# v11.net
KiCad netlist of a schematic drawn in EAGLE
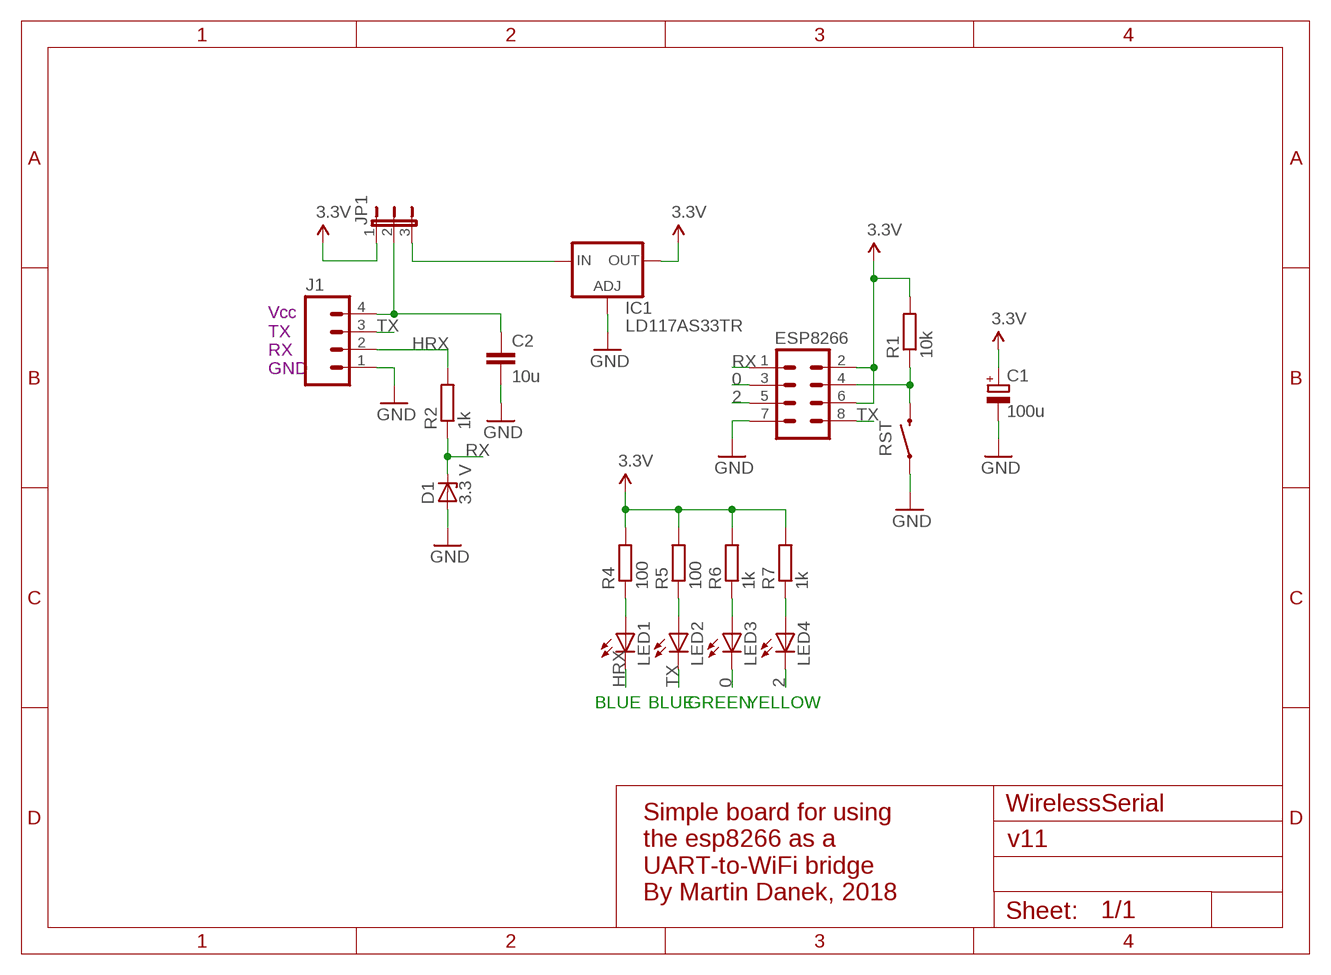
[diagram p0: schematic, sheet 1]

(export (version "E")
  (design (tool "Eeschema 10.0.6"))
  (components
    (comp (ref "C1")
      (value "100u")
      (footprint "eagle-import:E2,5-6E")
      (libsource (lib "eagle-import") (part "CPOL-EUE2,5-6E"))
    )
    (comp (ref "C2")
      (value "10u")
      (footprint "eagle-import:C1206")
      (libsource (lib "eagle-import") (part "C-EUC1206"))
    )
    (comp (ref "D1")
      (value "3.3 V")
      (footprint "eagle-import:DO35Z10")
      (libsource (lib "eagle-import") (part "ZENER-DIODEDO35Z10"))
    )
    (comp (ref "ESP8266")
      (value "M04X2")
      (footprint "eagle-import:2X4")
      (libsource (lib "eagle-import") (part "M04X2"))
    )
    (comp (ref "IC1")
      (value "LD117AS33TR")
      (footprint "eagle-import:SOT223")
      (libsource (lib "eagle-import") (part "LD117A?S33TR"))
    )
    (comp (ref "J1")
      (value "M04LONGPADS")
      (footprint "eagle-import:1X04_LONGPADS")
      (libsource (lib "eagle-import") (part "M04LONGPADS"))
    )
    (comp (ref "JP1")
      (value "JP2E")
      (footprint "eagle-import:JP2")
      (libsource (lib "eagle-import") (part "JP2E"))
    )
    (comp (ref "LED1")
      (value "LEDSML1206")
      (footprint "eagle-import:SML1206")
      (libsource (lib "eagle-import") (part "LEDSML1206"))
    )
    (comp (ref "LED2")
      (value "LEDSML1206")
      (footprint "eagle-import:SML1206")
      (libsource (lib "eagle-import") (part "LEDSML1206"))
    )
    (comp (ref "LED3")
      (value "LEDSML1206")
      (footprint "eagle-import:SML1206")
      (libsource (lib "eagle-import") (part "LEDSML1206"))
    )
    (comp (ref "LED4")
      (value "LEDSML1206")
      (footprint "eagle-import:SML1206")
      (libsource (lib "eagle-import") (part "LEDSML1206"))
    )
    (comp (ref "R1")
      (value "10k")
      (footprint "eagle-import:R1206")
      (libsource (lib "eagle-import") (part "R-EU_R1206"))
    )
    (comp (ref "R2")
      (value "1k")
      (footprint "eagle-import:R1206")
      (libsource (lib "eagle-import") (part "R-EU_R1206"))
    )
    (comp (ref "R4")
      (value "100")
      (footprint "eagle-import:R1206")
      (libsource (lib "eagle-import") (part "R-EU_R1206"))
    )
    (comp (ref "R5")
      (value "100")
      (footprint "eagle-import:R1206")
      (libsource (lib "eagle-import") (part "R-EU_R1206"))
    )
    (comp (ref "R6")
      (value "1k")
      (footprint "eagle-import:R1206")
      (libsource (lib "eagle-import") (part "R-EU_R1206"))
    )
    (comp (ref "R7")
      (value "1k")
      (footprint "eagle-import:R1206")
      (libsource (lib "eagle-import") (part "R-EU_R1206"))
    )
    (comp (ref "RST")
      (value "SWITCH-MOMENTARY-2PTH")
      (footprint "eagle-import:TACTILE-PTH")
      (libsource (lib "eagle-import") (part "SWITCH-MOMENTARY-2PTH"))
    )
  )
  (nets
    (net (code "1") (name "/0") (class "Default")
      (node (ref "ESP8266") (pin "3") (pinfunction "3_3") (pintype "passive"))
      (node (ref "LED3") (pin "C") (pinfunction "C_C") (pintype "passive"))
    )
    (net (code "2") (name "/2") (class "Default")
      (node (ref "ESP8266") (pin "5") (pinfunction "5_5") (pintype "passive"))
      (node (ref "LED4") (pin "C") (pinfunction "C_C") (pintype "passive"))
    )
    (net (code "3") (name "/HRX") (class "Default")
      (node (ref "J1") (pin "2") (pinfunction "2_2") (pintype "passive"))
      (node (ref "LED1") (pin "C") (pinfunction "C_C") (pintype "passive"))
      (node (ref "R2") (pin "2") (pinfunction "2_2") (pintype "passive"))
    )
    (net (code "4") (name "/RX") (class "Default")
      (node (ref "D1") (pin "C") (pinfunction "C_C") (pintype "passive"))
      (node (ref "ESP8266") (pin "1") (pinfunction "1_1") (pintype "passive"))
      (node (ref "R2") (pin "1") (pinfunction "1_1") (pintype "passive"))
    )
    (net (code "5") (name "/TX") (class "Default")
      (node (ref "ESP8266") (pin "8") (pinfunction "8_8") (pintype "passive"))
      (node (ref "J1") (pin "3") (pinfunction "3_3") (pintype "passive"))
      (node (ref "LED2") (pin "C") (pinfunction "C_C") (pintype "passive"))
    )
    (net (code "6") (name "3.3V") (class "Default")
      (node (ref "C1") (pin "+") (pinfunction "+_+") (pintype "passive"))
      (node (ref "ESP8266") (pin "2") (pinfunction "2_2") (pintype "passive"))
      (node (ref "ESP8266") (pin "6") (pinfunction "6_6") (pintype "passive"))
      (node (ref "IC1") (pin "4") (pinfunction "OUT_4") (pintype "passive"))
      (node (ref "JP1") (pin "1") (pinfunction "1_1") (pintype "passive"))
      (node (ref "R1") (pin "2") (pinfunction "2_2") (pintype "passive"))
      (node (ref "R4") (pin "2") (pinfunction "2_2") (pintype "passive"))
      (node (ref "R5") (pin "2") (pinfunction "2_2") (pintype "passive"))
      (node (ref "R6") (pin "2") (pinfunction "2_2") (pintype "passive"))
      (node (ref "R7") (pin "2") (pinfunction "2_2") (pintype "passive"))
    )
    (net (code "7") (name "GND") (class "Default")
      (node (ref "C1") (pin "-") (pinfunction "-_-") (pintype "passive"))
      (node (ref "C2") (pin "2") (pinfunction "2_2") (pintype "passive"))
      (node (ref "D1") (pin "A") (pinfunction "A_A") (pintype "passive"))
      (node (ref "ESP8266") (pin "7") (pinfunction "7_7") (pintype "passive"))
      (node (ref "IC1") (pin "1") (pinfunction "ADJ_1") (pintype "input"))
      (node (ref "J1") (pin "1") (pinfunction "1_1") (pintype "passive"))
      (node (ref "RST") (pin "1") (pinfunction "1_1") (pintype "passive"))
    )
    (net (code "8") (name "Net-(C2-Pad1)") (class "Default")
      (node (ref "C2") (pin "1") (pinfunction "1_1") (pintype "passive"))
      (node (ref "J1") (pin "4") (pinfunction "4_4") (pintype "passive"))
      (node (ref "JP1") (pin "2") (pinfunction "2_2") (pintype "passive"))
    )
    (net (code "9") (name "Net-(IC1-IN)") (class "Default")
      (node (ref "IC1") (pin "3") (pinfunction "IN_3") (pintype "input"))
      (node (ref "JP1") (pin "3") (pinfunction "3_3") (pintype "passive"))
    )
    (net (code "10") (name "Net-(LED1-PadA)") (class "Default")
      (node (ref "LED1") (pin "A") (pinfunction "A_A") (pintype "passive"))
      (node (ref "R4") (pin "1") (pinfunction "1_1") (pintype "passive"))
    )
    (net (code "11") (name "Net-(LED2-PadA)") (class "Default")
      (node (ref "LED2") (pin "A") (pinfunction "A_A") (pintype "passive"))
      (node (ref "R5") (pin "1") (pinfunction "1_1") (pintype "passive"))
    )
    (net (code "12") (name "Net-(LED3-PadA)") (class "Default")
      (node (ref "LED3") (pin "A") (pinfunction "A_A") (pintype "passive"))
      (node (ref "R6") (pin "1") (pinfunction "1_1") (pintype "passive"))
    )
    (net (code "13") (name "Net-(LED4-PadA)") (class "Default")
      (node (ref "LED4") (pin "A") (pinfunction "A_A") (pintype "passive"))
      (node (ref "R7") (pin "1") (pinfunction "1_1") (pintype "passive"))
    )
    (net (code "14") (name "Net-(RST-2)") (class "Default")
      (node (ref "ESP8266") (pin "4") (pinfunction "4_4") (pintype "passive"))
      (node (ref "R1") (pin "1") (pinfunction "1_1") (pintype "passive"))
      (node (ref "RST") (pin "3") (pinfunction "2_3") (pintype "passive"))
    )
  )
)
